# SCH_MACROPAD.net
KiCad netlist of a schematic drawn in EasyEDA
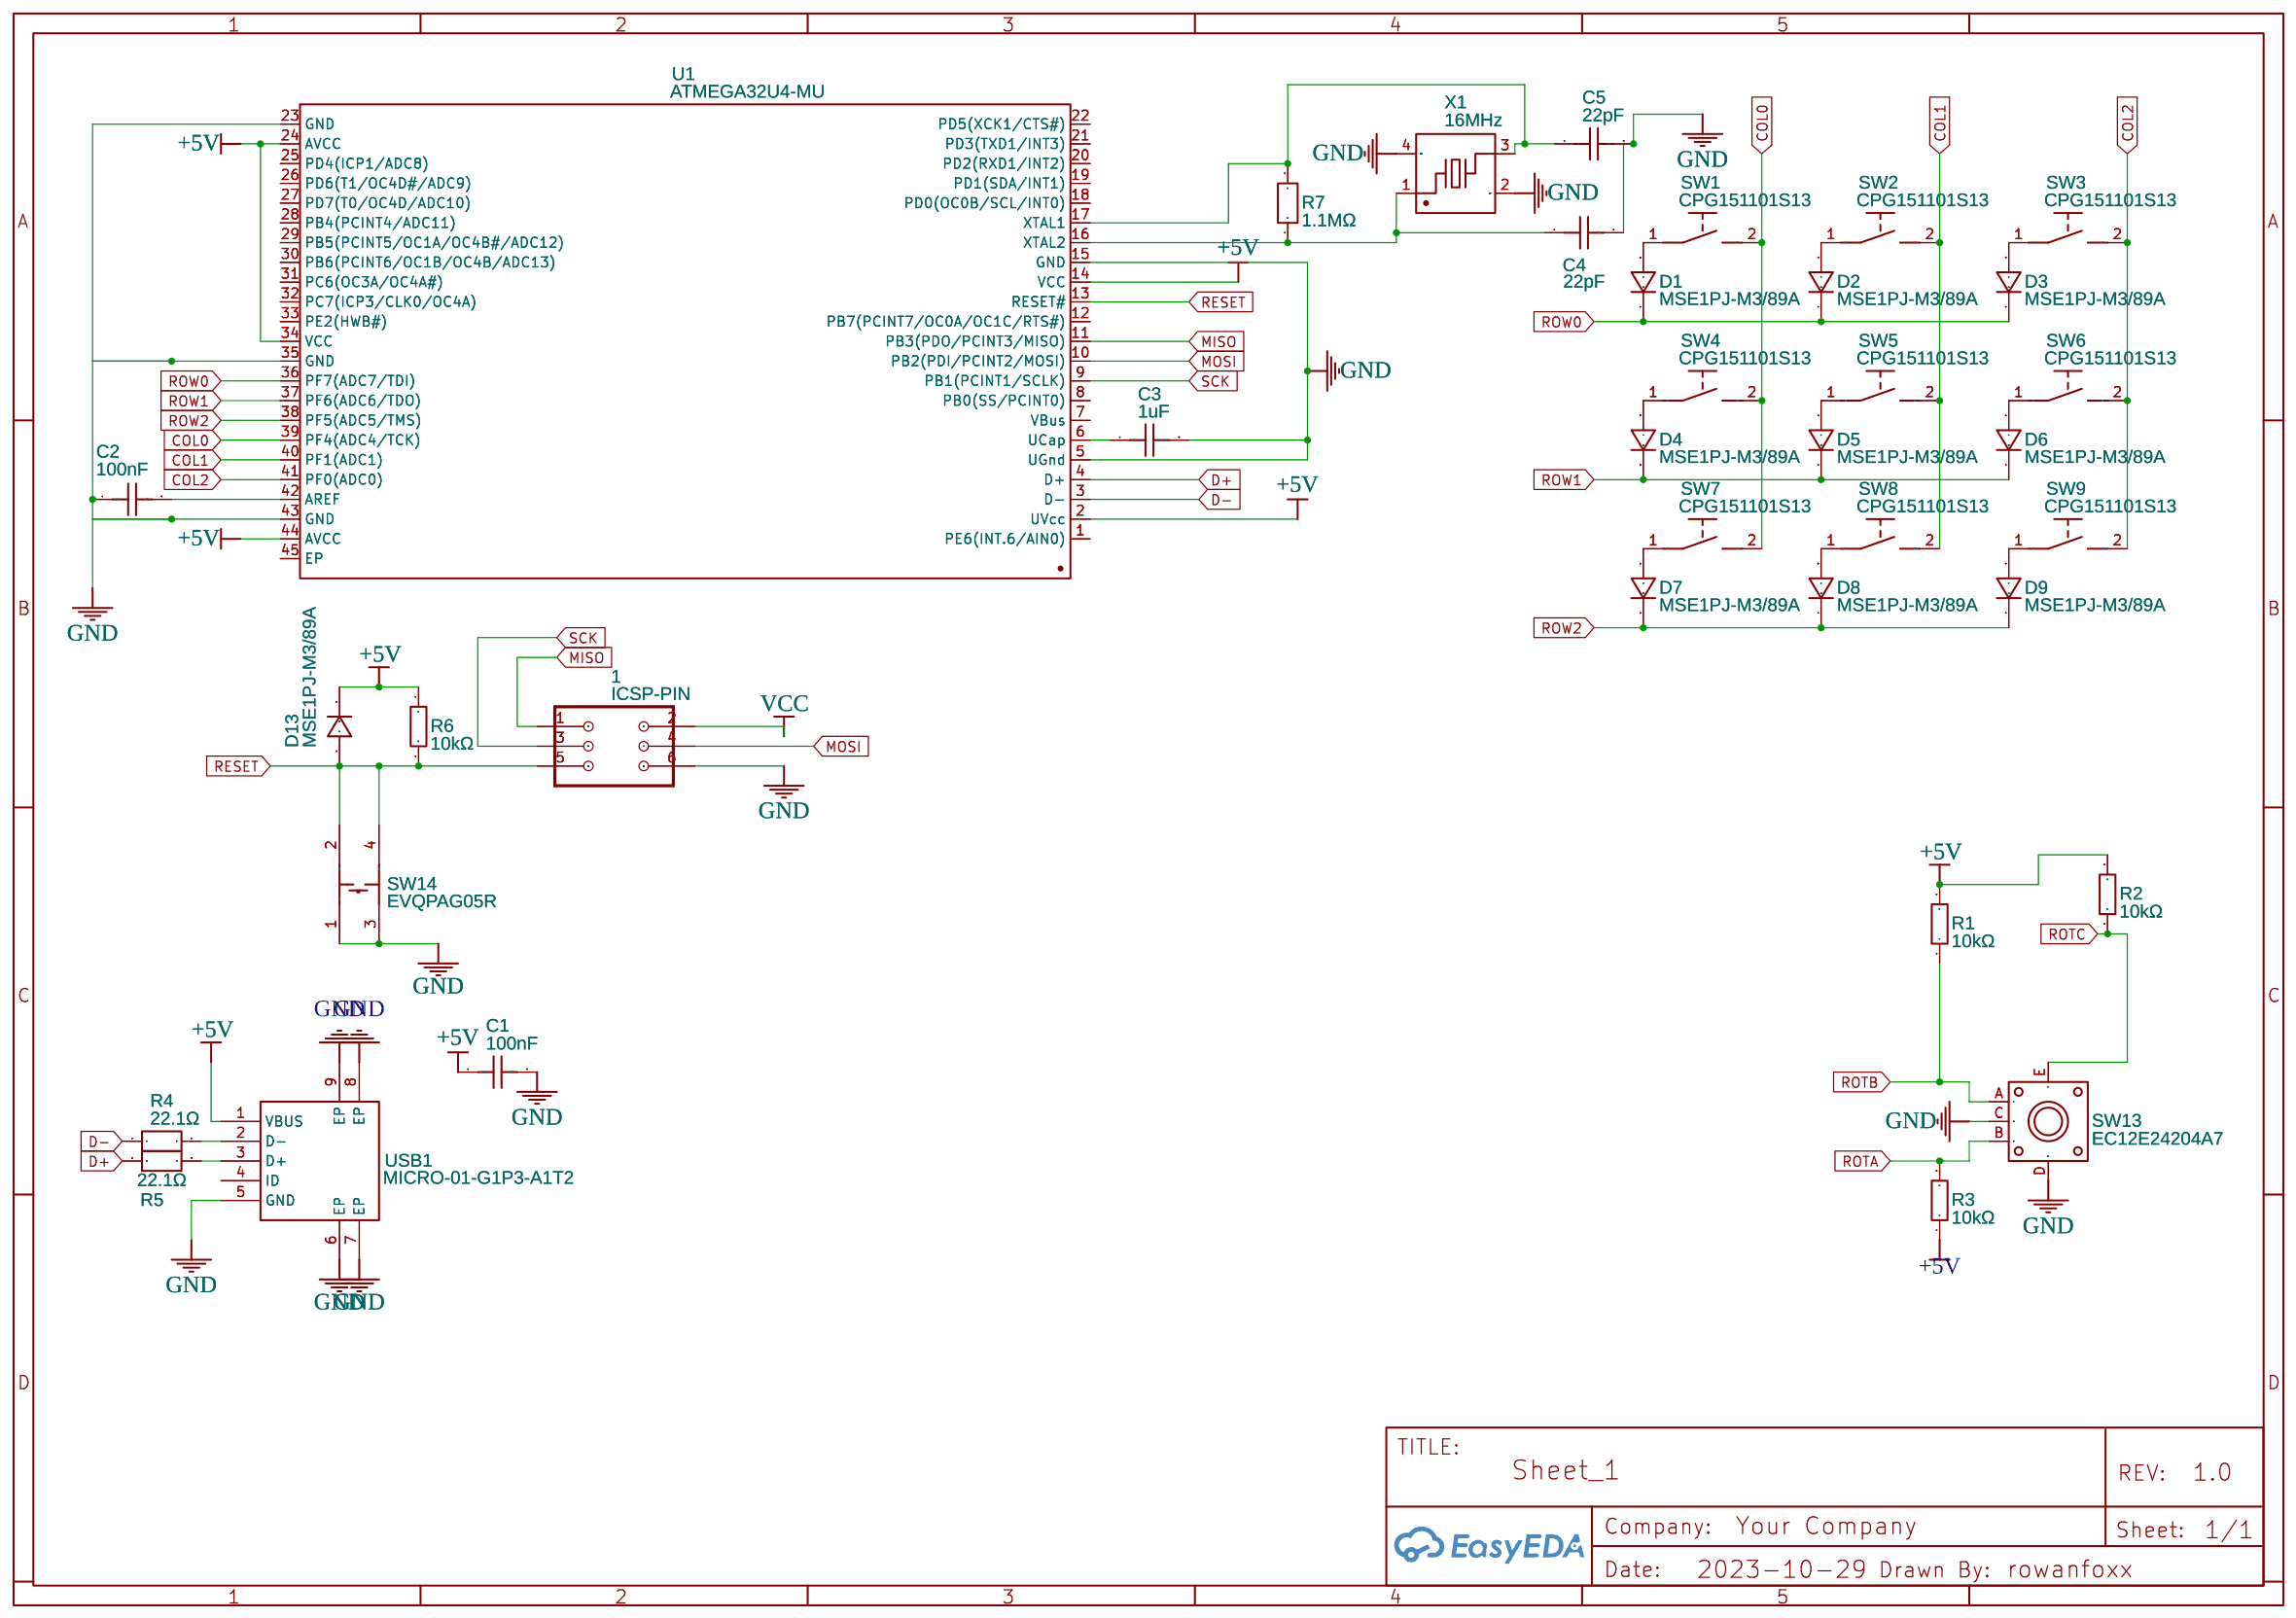
[diagram p0: schematic sheet]

(export (version "E")
  (design (tool "Eeschema 10.0.6"))
  (components
    (comp (ref "1") (value "ICSP-PIN") (libsource (lib "") (part "ICSP-PIN")))
    (comp (ref "C1")
      (value "100nF")
      (fields (field (name "Manufacturer Part") "MT15B104K160CT") (field (name "Manufacturer") "Walsin(华新科)"))
      (libsource (lib "") (part "MT15B104K160CT"))
    )
    (comp (ref "C2")
      (value "100nF")
      (fields (field (name "Manufacturer Part") "MT15B104K160CT") (field (name "Manufacturer") "Walsin(华新科)"))
      (libsource (lib "") (part "MT15B104K160CT"))
    )
    (comp (ref "C3")
      (value "1uF")
      (fields (field (name "Manufacturer Part") "FS15B105K6R3PNG") (field (name "Manufacturer") "PSA(信昌电陶)"))
      (libsource (lib "") (part "FS15B105K6R3PNG"))
    )
    (comp (ref "C4")
      (value "22pF")
      (fields
        (field (name "Manufacturer Part") "UMK105CG220JV-F")
        (field (name "Manufacturer") "TAIYO YUDEN(太诱)")
      )
      (libsource (lib "") (part "UMK105CG220JV-F"))
    )
    (comp (ref "C5")
      (value "22pF")
      (fields
        (field (name "Manufacturer Part") "UMK105CG220JV-F")
        (field (name "Manufacturer") "TAIYO YUDEN(太诱)")
      )
      (libsource (lib "") (part "UMK105CG220JV-F"))
    )
    (comp (ref "D1")
      (value "MSE1PJ-M3/89A")
      (fields (field (name "Manufacturer Part") "1N4007W") (field (name "Manufacturer") "BLUE ROCKET(蓝箭)"))
      (libsource (lib "") (part "MSE1PJ-M3/89A"))
    )
    (comp (ref "D2")
      (value "MSE1PJ-M3/89A")
      (fields (field (name "Manufacturer Part") "1N4007W") (field (name "Manufacturer") "BLUE ROCKET(蓝箭)"))
      (libsource (lib "") (part "MSE1PJ-M3/89A"))
    )
    (comp (ref "D3")
      (value "MSE1PJ-M3/89A")
      (fields (field (name "Manufacturer Part") "1N4007W") (field (name "Manufacturer") "BLUE ROCKET(蓝箭)"))
      (libsource (lib "") (part "MSE1PJ-M3/89A"))
    )
    (comp (ref "D4")
      (value "MSE1PJ-M3/89A")
      (fields (field (name "Manufacturer Part") "1N4007W") (field (name "Manufacturer") "BLUE ROCKET(蓝箭)"))
      (libsource (lib "") (part "MSE1PJ-M3/89A"))
    )
    (comp (ref "D5")
      (value "MSE1PJ-M3/89A")
      (fields (field (name "Manufacturer Part") "1N4007W") (field (name "Manufacturer") "BLUE ROCKET(蓝箭)"))
      (libsource (lib "") (part "MSE1PJ-M3/89A"))
    )
    (comp (ref "D6")
      (value "MSE1PJ-M3/89A")
      (fields (field (name "Manufacturer Part") "1N4007W") (field (name "Manufacturer") "BLUE ROCKET(蓝箭)"))
      (libsource (lib "") (part "MSE1PJ-M3/89A"))
    )
    (comp (ref "D7")
      (value "MSE1PJ-M3/89A")
      (fields (field (name "Manufacturer Part") "1N4007W") (field (name "Manufacturer") "BLUE ROCKET(蓝箭)"))
      (libsource (lib "") (part "MSE1PJ-M3/89A"))
    )
    (comp (ref "D8")
      (value "MSE1PJ-M3/89A")
      (fields (field (name "Manufacturer Part") "1N4007W") (field (name "Manufacturer") "BLUE ROCKET(蓝箭)"))
      (libsource (lib "") (part "MSE1PJ-M3/89A"))
    )
    (comp (ref "D9")
      (value "MSE1PJ-M3/89A")
      (fields (field (name "Manufacturer Part") "1N4007W") (field (name "Manufacturer") "BLUE ROCKET(蓝箭)"))
      (libsource (lib "") (part "MSE1PJ-M3/89A"))
    )
    (comp (ref "D13")
      (value "MSE1PJ-M3/89A")
      (fields (field (name "Manufacturer Part") "1N4007W") (field (name "Manufacturer") "BLUE ROCKET(蓝箭)"))
      (libsource (lib "") (part "MSE1PJ-M3/89A_1"))
    )
    (comp (ref "R1")
      (value "10kΩ")
      (fields (field (name "Manufacturer Part") "RCT0610KFLF") (field (name "Manufacturer") "HKR"))
      (libsource (lib "") (part "RM06JTN103_1"))
    )
    (comp (ref "R2")
      (value "10kΩ")
      (fields (field (name "Manufacturer Part") "RCT0610KFLF") (field (name "Manufacturer") "HKR"))
      (libsource (lib "") (part "RM06JTN103_1"))
    )
    (comp (ref "R3")
      (value "10kΩ")
      (fields (field (name "Manufacturer Part") "RCT0610KFLF") (field (name "Manufacturer") "HKR"))
      (libsource (lib "") (part "RM06JTN103_1"))
    )
    (comp (ref "R4")
      (value "22.1Ω")
      (fields
        (field (name "Manufacturer Part") "1210W2F221JT5E")
        (field (name "Manufacturer") "UNI-ROYAL(厚声)")
      )
      (libsource (lib "") (part "1210W2F221JT5E"))
    )
    (comp (ref "R5")
      (value "22.1Ω")
      (fields
        (field (name "Manufacturer Part") "1210W2F221JT5E")
        (field (name "Manufacturer") "UNI-ROYAL(厚声)")
      )
      (libsource (lib "") (part "1210W2F221JT5E"))
    )
    (comp (ref "R6")
      (value "10kΩ")
      (fields (field (name "Manufacturer Part") "RCT0610KFLF") (field (name "Manufacturer") "HKR"))
      (libsource (lib "") (part "RM06JTN103"))
    )
    (comp (ref "R7")
      (value "1.1MΩ")
      (fields (field (name "Manufacturer Part") "WR08X115JTL") (field (name "Manufacturer") "Walsin(华新科)"))
      (libsource (lib "") (part "WR08X115JTL"))
    )
    (comp (ref "SW1")
      (value "CPG151101S13")
      (fields (field (name "Manufacturer Part") "CPG151101D91") (field (name "Manufacturer") "Kailh(凯华)"))
      (libsource (lib "") (part "CPG151101S13"))
    )
    (comp (ref "SW2")
      (value "CPG151101S13")
      (fields (field (name "Manufacturer Part") "CPG151101D91") (field (name "Manufacturer") "Kailh(凯华)"))
      (libsource (lib "") (part "CPG151101S13"))
    )
    (comp (ref "SW3")
      (value "CPG151101S13")
      (fields (field (name "Manufacturer Part") "CPG151101D91") (field (name "Manufacturer") "Kailh(凯华)"))
      (libsource (lib "") (part "CPG151101S13"))
    )
    (comp (ref "SW4")
      (value "CPG151101S13")
      (fields (field (name "Manufacturer Part") "CPG151101D91") (field (name "Manufacturer") "Kailh(凯华)"))
      (libsource (lib "") (part "CPG151101S13"))
    )
    (comp (ref "SW5")
      (value "CPG151101S13")
      (fields (field (name "Manufacturer Part") "CPG151101D91") (field (name "Manufacturer") "Kailh(凯华)"))
      (libsource (lib "") (part "CPG151101S13"))
    )
    (comp (ref "SW6")
      (value "CPG151101S13")
      (fields (field (name "Manufacturer Part") "CPG151101D91") (field (name "Manufacturer") "Kailh(凯华)"))
      (libsource (lib "") (part "CPG151101S13"))
    )
    (comp (ref "SW7")
      (value "CPG151101S13")
      (fields (field (name "Manufacturer Part") "CPG151101D91") (field (name "Manufacturer") "Kailh(凯华)"))
      (libsource (lib "") (part "CPG151101S13"))
    )
    (comp (ref "SW8")
      (value "CPG151101S13")
      (fields (field (name "Manufacturer Part") "CPG151101D91") (field (name "Manufacturer") "Kailh(凯华)"))
      (libsource (lib "") (part "CPG151101S13"))
    )
    (comp (ref "SW9")
      (value "CPG151101S13")
      (fields (field (name "Manufacturer Part") "CPG151101D91") (field (name "Manufacturer") "Kailh(凯华)"))
      (libsource (lib "") (part "CPG151101S13"))
    )
    (comp (ref "SW13")
      (value "EC12E24204A7")
      (fields (field (name "Manufacturer") "ALPSALPINE(阿尔卑斯阿尔派)"))
      (libsource (lib "") (part "EC12E24204A7"))
    )
    (comp (ref "SW14")
      (value "EVQPAG05R")
      (fields (field (name "Manufacturer") "PANASONIC(松下)"))
      (libsource (lib "") (part "EVQPAG05R"))
    )
    (comp (ref "U1")
      (value "ATMEGA32U4-MU")
      (fields (field (name "Manufacturer") "MICROCHIP(美国微芯)"))
      (libsource (lib "") (part "ATMEGA32U4-MU"))
    )
    (comp (ref "USB1")
      (value "MICRO-01-G1P3-A1T2")
      (fields (field (name "Manufacturer") "Yuandi(元迪)"))
      (libsource (lib "") (part "MICRO-01-G1P3-A1T2"))
    )
    (comp (ref "X1")
      (value "16MHz")
      (fields (field (name "Manufacturer Part") "7B016000H01") (field (name "Manufacturer") "HD(浩都频率)"))
      (libsource (lib "") (part "7B016000H01"))
    )
  )
  (nets
    (net (code "1") (name "+5V") (class "Default")
      (node (ref "C1") (pin "1") (pinfunction "1_1") (pintype "unspecified"))
      (node (ref "D13") (pin "1") (pinfunction "C_1") (pintype "unspecified"))
      (node (ref "R1") (pin "2") (pinfunction "2_2") (pintype "input"))
      (node (ref "R2") (pin "2") (pinfunction "2_2") (pintype "input"))
      (node (ref "R3") (pin "1") (pinfunction "1_1") (pintype "input"))
      (node (ref "R6") (pin "1") (pinfunction "1_1") (pintype "input"))
      (node (ref "U1") (pin "14") (pinfunction "VCC_14") (pintype "unspecified"))
      (node (ref "U1") (pin "2") (pinfunction "UVcc_2") (pintype "unspecified"))
      (node (ref "U1") (pin "24") (pinfunction "AVCC_24") (pintype "unspecified"))
      (node (ref "U1") (pin "34") (pinfunction "VCC_34") (pintype "unspecified"))
      (node (ref "U1") (pin "44") (pinfunction "AVCC_44") (pintype "unspecified"))
      (node (ref "USB1") (pin "1") (pinfunction "VBUS_1") (pintype "unspecified"))
    )
    (net (code "2") (name "COL0") (class "Default")
      (node (ref "SW1") (pin "2") (pinfunction "2_2") (pintype "unspecified"))
      (node (ref "SW4") (pin "2") (pinfunction "2_2") (pintype "unspecified"))
      (node (ref "SW7") (pin "2") (pinfunction "2_2") (pintype "unspecified"))
      (node (ref "U1") (pin "39") (pinfunction "PF4(ADC4/TCK)_39") (pintype "unspecified"))
    )
    (net (code "3") (name "COL1") (class "Default")
      (node (ref "SW2") (pin "2") (pinfunction "2_2") (pintype "unspecified"))
      (node (ref "SW5") (pin "2") (pinfunction "2_2") (pintype "unspecified"))
      (node (ref "SW8") (pin "2") (pinfunction "2_2") (pintype "unspecified"))
      (node (ref "U1") (pin "40") (pinfunction "PF1(ADC1)_40") (pintype "unspecified"))
    )
    (net (code "4") (name "COL2") (class "Default")
      (node (ref "SW3") (pin "2") (pinfunction "2_2") (pintype "unspecified"))
      (node (ref "SW6") (pin "2") (pinfunction "2_2") (pintype "unspecified"))
      (node (ref "SW9") (pin "2") (pinfunction "2_2") (pintype "unspecified"))
      (node (ref "U1") (pin "41") (pinfunction "PF0(ADC0)_41") (pintype "unspecified"))
    )
    (net (code "5") (name "D+") (class "Default")
      (node (ref "R5") (pin "1") (pinfunction "1_1") (pintype "unspecified"))
      (node (ref "U1") (pin "4") (pinfunction "D+_4") (pintype "unspecified"))
    )
    (net (code "6") (name "D-") (class "Default")
      (node (ref "R4") (pin "1") (pinfunction "1_1") (pintype "unspecified"))
      (node (ref "U1") (pin "3") (pinfunction "D-_3") (pintype "unspecified"))
    )
    (net (code "7") (name "GND") (class "Default")
      (node (ref "1") (pin "6") (pinfunction "6_6") (pintype "bidirectional"))
      (node (ref "C1") (pin "2") (pinfunction "2_2") (pintype "unspecified"))
      (node (ref "C2") (pin "1") (pinfunction "1_1") (pintype "unspecified"))
      (node (ref "C3") (pin "2") (pinfunction "2_2") (pintype "unspecified"))
      (node (ref "C4") (pin "2") (pinfunction "2_2") (pintype "unspecified"))
      (node (ref "C5") (pin "2") (pinfunction "2_2") (pintype "unspecified"))
      (node (ref "SW13") (pin "C") (pinfunction "C_C") (pintype "unspecified"))
      (node (ref "SW13") (pin "D") (pinfunction "D_D") (pintype "unspecified"))
      (node (ref "SW14") (pin "1") (pinfunction "1_1") (pintype "unspecified"))
      (node (ref "SW14") (pin "3") (pinfunction "3_3") (pintype "unspecified"))
      (node (ref "U1") (pin "15") (pinfunction "GND_15") (pintype "unspecified"))
      (node (ref "U1") (pin "23") (pinfunction "GND_23") (pintype "unspecified"))
      (node (ref "U1") (pin "35") (pinfunction "GND_35") (pintype "unspecified"))
      (node (ref "U1") (pin "43") (pinfunction "GND_43") (pintype "unspecified"))
      (node (ref "U1") (pin "5") (pinfunction "UGnd_5") (pintype "unspecified"))
      (node (ref "USB1") (pin "5") (pinfunction "GND_5") (pintype "unspecified"))
      (node (ref "USB1") (pin "6") (pinfunction "EP_6") (pintype "unspecified"))
      (node (ref "USB1") (pin "7") (pinfunction "EP_7") (pintype "unspecified"))
      (node (ref "USB1") (pin "8") (pinfunction "EP_8") (pintype "unspecified"))
      (node (ref "USB1") (pin "9") (pinfunction "EP_9") (pintype "unspecified"))
      (node (ref "X1") (pin "2") (pinfunction "GND_2") (pintype "input"))
      (node (ref "X1") (pin "4") (pinfunction "GND_4") (pintype "input"))
    )
    (net (code "8") (name "MISO") (class "Default")
      (node (ref "1") (pin "1") (pinfunction "1_1") (pintype "bidirectional"))
      (node (ref "U1") (pin "11") (pinfunction "PB3(PDO/PCINT3/MISO)_11") (pintype "unspecified"))
    )
    (net (code "9") (name "MOSI") (class "Default")
      (node (ref "1") (pin "4") (pinfunction "4_4") (pintype "bidirectional"))
      (node (ref "U1") (pin "10") (pinfunction "PB2(PDI/PCINT2/MOSI)_10") (pintype "unspecified"))
    )
    (net (code "10") (name "Net-(D1-A)") (class "Default")
      (node (ref "D1") (pin "2") (pinfunction "A_2") (pintype "unspecified"))
      (node (ref "SW1") (pin "1") (pinfunction "1_1") (pintype "unspecified"))
    )
    (net (code "11") (name "Net-(D2-A)") (class "Default")
      (node (ref "D2") (pin "2") (pinfunction "A_2") (pintype "unspecified"))
      (node (ref "SW2") (pin "1") (pinfunction "1_1") (pintype "unspecified"))
    )
    (net (code "12") (name "Net-(D3-A)") (class "Default")
      (node (ref "D3") (pin "2") (pinfunction "A_2") (pintype "unspecified"))
      (node (ref "SW3") (pin "1") (pinfunction "1_1") (pintype "unspecified"))
    )
    (net (code "13") (name "Net-(D4-A)") (class "Default")
      (node (ref "D4") (pin "2") (pinfunction "A_2") (pintype "unspecified"))
      (node (ref "SW4") (pin "1") (pinfunction "1_1") (pintype "unspecified"))
    )
    (net (code "14") (name "Net-(D5-A)") (class "Default")
      (node (ref "D5") (pin "2") (pinfunction "A_2") (pintype "unspecified"))
      (node (ref "SW5") (pin "1") (pinfunction "1_1") (pintype "unspecified"))
    )
    (net (code "15") (name "Net-(D6-A)") (class "Default")
      (node (ref "D6") (pin "2") (pinfunction "A_2") (pintype "unspecified"))
      (node (ref "SW6") (pin "1") (pinfunction "1_1") (pintype "unspecified"))
    )
    (net (code "16") (name "Net-(D7-A)") (class "Default")
      (node (ref "D7") (pin "2") (pinfunction "A_2") (pintype "unspecified"))
      (node (ref "SW7") (pin "1") (pinfunction "1_1") (pintype "unspecified"))
    )
    (net (code "17") (name "Net-(D8-A)") (class "Default")
      (node (ref "D8") (pin "2") (pinfunction "A_2") (pintype "unspecified"))
      (node (ref "SW8") (pin "1") (pinfunction "1_1") (pintype "unspecified"))
    )
    (net (code "18") (name "Net-(D9-A)") (class "Default")
      (node (ref "D9") (pin "2") (pinfunction "A_2") (pintype "unspecified"))
      (node (ref "SW9") (pin "1") (pinfunction "1_1") (pintype "unspecified"))
    )
    (net (code "19") (name "Net-(U1-AREF)") (class "Default")
      (node (ref "C2") (pin "2") (pinfunction "2_2") (pintype "unspecified"))
      (node (ref "U1") (pin "42") (pinfunction "AREF_42") (pintype "unspecified"))
    )
    (net (code "20") (name "Net-(U1-UCap)") (class "Default")
      (node (ref "C3") (pin "1") (pinfunction "1_1") (pintype "unspecified"))
      (node (ref "U1") (pin "6") (pinfunction "UCap_6") (pintype "unspecified"))
    )
    (net (code "21") (name "Net-(U1-XTAL1)") (class "Default")
      (node (ref "C5") (pin "1") (pinfunction "1_1") (pintype "unspecified"))
      (node (ref "R7") (pin "2") (pinfunction "2_2") (pintype "unspecified"))
      (node (ref "U1") (pin "17") (pinfunction "XTAL1_17") (pintype "unspecified"))
      (node (ref "X1") (pin "3") (pinfunction "OUT_3") (pintype "input"))
    )
    (net (code "22") (name "Net-(U1-XTAL2)") (class "Default")
      (node (ref "C4") (pin "1") (pinfunction "1_1") (pintype "unspecified"))
      (node (ref "R7") (pin "1") (pinfunction "1_1") (pintype "unspecified"))
      (node (ref "U1") (pin "16") (pinfunction "XTAL2_16") (pintype "unspecified"))
      (node (ref "X1") (pin "1") (pinfunction "IN_1") (pintype "input"))
    )
    (net (code "23") (name "Net-(USB1-D+)") (class "Default")
      (node (ref "R5") (pin "2") (pinfunction "2_2") (pintype "unspecified"))
      (node (ref "USB1") (pin "3") (pinfunction "D+_3") (pintype "unspecified"))
    )
    (net (code "24") (name "Net-(USB1-D-)") (class "Default")
      (node (ref "R4") (pin "2") (pinfunction "2_2") (pintype "unspecified"))
      (node (ref "USB1") (pin "2") (pinfunction "D-_2") (pintype "unspecified"))
    )
    (net (code "25") (name "RESET") (class "Default")
      (node (ref "1") (pin "5") (pinfunction "5_5") (pintype "bidirectional"))
      (node (ref "D13") (pin "2") (pinfunction "A_2") (pintype "unspecified"))
      (node (ref "R6") (pin "2") (pinfunction "2_2") (pintype "input"))
      (node (ref "SW14") (pin "2") (pinfunction "2_2") (pintype "unspecified"))
      (node (ref "SW14") (pin "4") (pinfunction "4_4") (pintype "unspecified"))
      (node (ref "U1") (pin "13") (pinfunction "RESET#_13") (pintype "unspecified"))
    )
    (net (code "26") (name "ROTA") (class "Default")
      (node (ref "R3") (pin "2") (pinfunction "2_2") (pintype "input"))
      (node (ref "SW13") (pin "B") (pinfunction "B_B") (pintype "unspecified"))
    )
    (net (code "27") (name "ROTB") (class "Default")
      (node (ref "R1") (pin "1") (pinfunction "1_1") (pintype "input"))
      (node (ref "SW13") (pin "A") (pinfunction "A_A") (pintype "unspecified"))
    )
    (net (code "28") (name "ROTC") (class "Default")
      (node (ref "R2") (pin "1") (pinfunction "1_1") (pintype "input"))
      (node (ref "SW13") (pin "E") (pinfunction "E_E") (pintype "unspecified"))
    )
    (net (code "29") (name "ROW0") (class "Default")
      (node (ref "D1") (pin "1") (pinfunction "C_1") (pintype "unspecified"))
      (node (ref "D2") (pin "1") (pinfunction "C_1") (pintype "unspecified"))
      (node (ref "D3") (pin "1") (pinfunction "C_1") (pintype "unspecified"))
      (node (ref "U1") (pin "36") (pinfunction "PF7(ADC7/TDI)_36") (pintype "unspecified"))
    )
    (net (code "30") (name "ROW1") (class "Default")
      (node (ref "D4") (pin "1") (pinfunction "C_1") (pintype "unspecified"))
      (node (ref "D5") (pin "1") (pinfunction "C_1") (pintype "unspecified"))
      (node (ref "D6") (pin "1") (pinfunction "C_1") (pintype "unspecified"))
      (node (ref "U1") (pin "37") (pinfunction "PF6(ADC6/TDO)_37") (pintype "unspecified"))
    )
    (net (code "31") (name "ROW2") (class "Default")
      (node (ref "D7") (pin "1") (pinfunction "C_1") (pintype "unspecified"))
      (node (ref "D8") (pin "1") (pinfunction "C_1") (pintype "unspecified"))
      (node (ref "D9") (pin "1") (pinfunction "C_1") (pintype "unspecified"))
      (node (ref "U1") (pin "38") (pinfunction "PF5(ADC5/TMS)_38") (pintype "unspecified"))
    )
    (net (code "32") (name "SCK") (class "Default")
      (node (ref "1") (pin "3") (pinfunction "3_3") (pintype "bidirectional"))
      (node (ref "U1") (pin "9") (pinfunction "PB1(PCINT1/SCLK)_9") (pintype "unspecified"))
    )
    (net (code "33") (name "VCC") (class "Default")
      (node (ref "1") (pin "2") (pinfunction "2_2") (pintype "bidirectional"))
    )
    (net (code "34") (name "unconnected-(U1-EP-Pad45)") (class "Default")
      (node (ref "U1") (pin "45") (pinfunction "EP_45") (pintype "unspecified"))
    )
    (net (code "35") (name "unconnected-(U1-PB0(SS{slash}PCINT0)-Pad8)") (class "Default")
      (node (ref "U1") (pin "8") (pinfunction "PB0(SS/PCINT0)_8") (pintype "unspecified"))
    )
    (net (code "36") (name "unconnected-(U1-PB4(PCINT4{slash}ADC11)-Pad28)") (class "Default")
      (node (ref "U1") (pin "28") (pinfunction "PB4(PCINT4/ADC11)_28") (pintype "unspecified"))
    )
    (net (code "37") (name "unconnected-(U1-PB5(PCINT5{slash}OC1A{slash}OC4B#{slash}ADC12)-Pad29)") (class "Default")
      (node (ref "U1") (pin "29") (pinfunction "PB5(PCINT5/OC1A/OC4B#/ADC12)_29") (pintype "unspecified"))
    )
    (net (code "38") (name "unconnected-(U1-PB6(PCINT6{slash}OC1B{slash}OC4B{slash}ADC13)-Pad30)") (class "Default")
      (node (ref "U1") (pin "30") (pinfunction "PB6(PCINT6/OC1B/OC4B/ADC13)_30") (pintype "unspecified"))
    )
    (net (code "39") (name "unconnected-(U1-PB7(PCINT7{slash}OC0A{slash}OC1C{slash}RTS#)-Pad12)") (class "Default")
      (node (ref "U1") (pin "12") (pinfunction "PB7(PCINT7/OC0A/OC1C/RTS#)_12") (pintype "unspecified"))
    )
    (net (code "40") (name "unconnected-(U1-PC6(OC3A{slash}OC4A#)-Pad31)") (class "Default")
      (node (ref "U1") (pin "31") (pinfunction "PC6(OC3A/OC4A#)_31") (pintype "unspecified"))
    )
    (net (code "41") (name "unconnected-(U1-PC7(ICP3{slash}CLK0{slash}OC4A)-Pad32)") (class "Default")
      (node (ref "U1") (pin "32") (pinfunction "PC7(ICP3/CLK0/OC4A)_32") (pintype "unspecified"))
    )
    (net (code "42") (name "unconnected-(U1-PD0(OC0B{slash}SCL{slash}INT0)-Pad18)") (class "Default")
      (node (ref "U1") (pin "18") (pinfunction "PD0(OC0B/SCL/INT0)_18") (pintype "unspecified"))
    )
    (net (code "43") (name "unconnected-(U1-PD1(SDA{slash}INT1)-Pad19)") (class "Default")
      (node (ref "U1") (pin "19") (pinfunction "PD1(SDA/INT1)_19") (pintype "unspecified"))
    )
    (net (code "44") (name "unconnected-(U1-PD2(RXD1{slash}INT2)-Pad20)") (class "Default")
      (node (ref "U1") (pin "20") (pinfunction "PD2(RXD1/INT2)_20") (pintype "unspecified"))
    )
    (net (code "45") (name "unconnected-(U1-PD3(TXD1{slash}INT3)-Pad21)") (class "Default")
      (node (ref "U1") (pin "21") (pinfunction "PD3(TXD1/INT3)_21") (pintype "unspecified"))
    )
    (net (code "46") (name "unconnected-(U1-PD4(ICP1{slash}ADC8)-Pad25)") (class "Default")
      (node (ref "U1") (pin "25") (pinfunction "PD4(ICP1/ADC8)_25") (pintype "unspecified"))
    )
    (net (code "47") (name "unconnected-(U1-PD5(XCK1{slash}CTS#)-Pad22)") (class "Default")
      (node (ref "U1") (pin "22") (pinfunction "PD5(XCK1/CTS#)_22") (pintype "unspecified"))
    )
    (net (code "48") (name "unconnected-(U1-PD6(T1{slash}OC4D#{slash}ADC9)-Pad26)") (class "Default")
      (node (ref "U1") (pin "26") (pinfunction "PD6(T1/OC4D#/ADC9)_26") (pintype "unspecified"))
    )
    (net (code "49") (name "unconnected-(U1-PD7(T0{slash}OC4D{slash}ADC10)-Pad27)") (class "Default")
      (node (ref "U1") (pin "27") (pinfunction "PD7(T0/OC4D/ADC10)_27") (pintype "unspecified"))
    )
    (net (code "50") (name "unconnected-(U1-PE2(HWB#)-Pad33)") (class "Default")
      (node (ref "U1") (pin "33") (pinfunction "PE2(HWB#)_33") (pintype "unspecified"))
    )
    (net (code "51") (name "unconnected-(U1-PE6(INT.6{slash}AIN0)-Pad1)") (class "Default")
      (node (ref "U1") (pin "1") (pinfunction "PE6(INT.6/AIN0)_1") (pintype "unspecified"))
    )
    (net (code "52") (name "unconnected-(U1-VBus-Pad7)") (class "Default")
      (node (ref "U1") (pin "7") (pinfunction "VBus_7") (pintype "unspecified"))
    )
    (net (code "53") (name "unconnected-(USB1-ID-Pad4)") (class "Default")
      (node (ref "USB1") (pin "4") (pinfunction "ID_4") (pintype "unspecified"))
    )
  )
)
